# ear-o_board.net
KiCad netlist of a schematic drawn in EAGLE
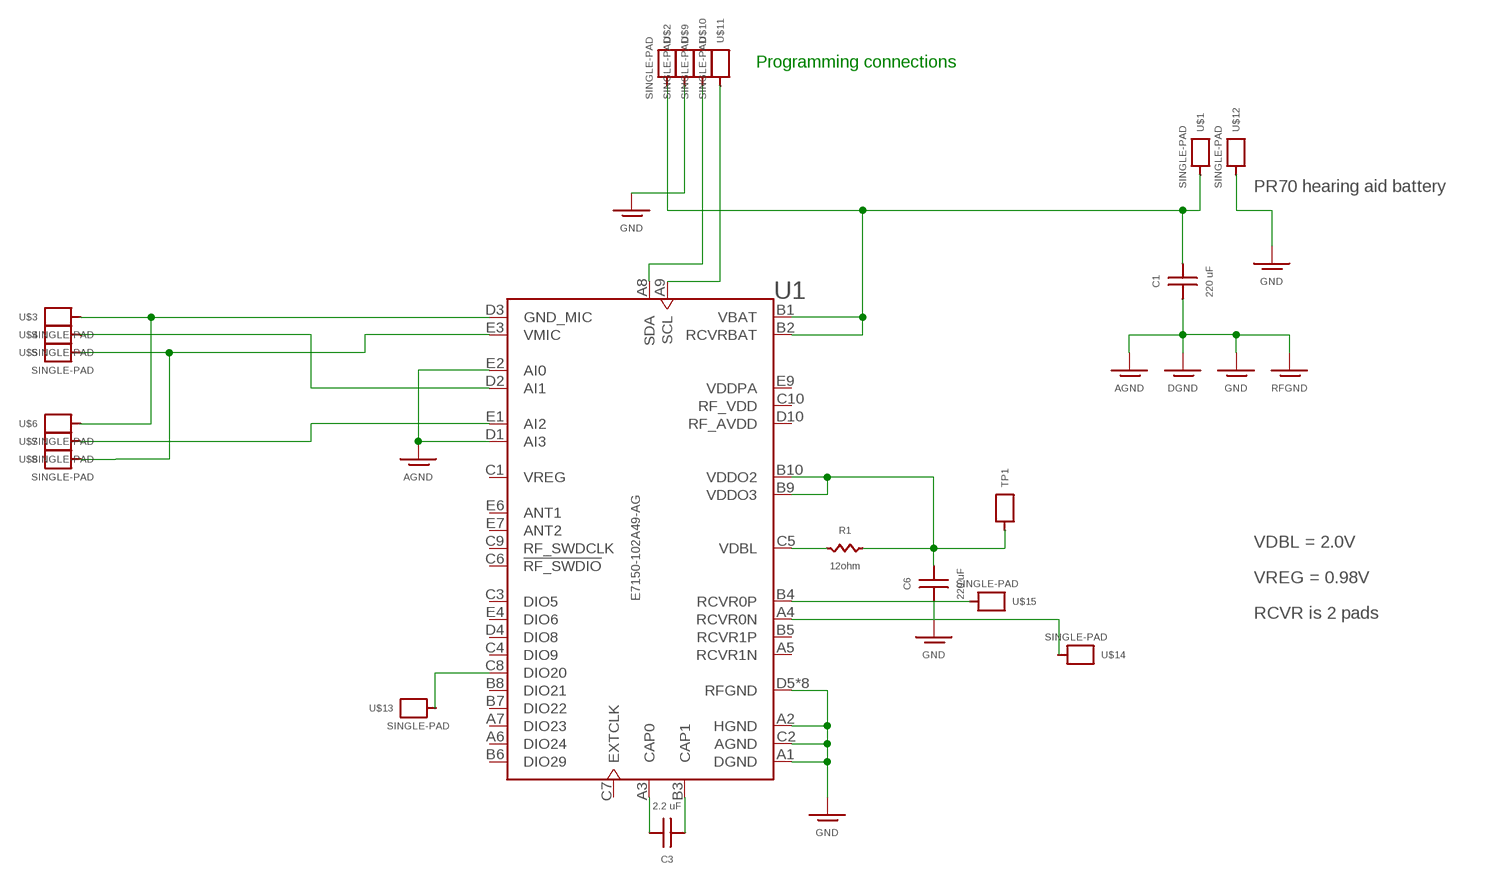
[diagram p0: schematic, sheet 1]

(export (version "E")
  (design (tool "Eeschema 10.0.6"))
  (components
    (comp (ref "C1")
      (value "220 uF")
      (footprint "eagle-import:1206")
      (libsource (lib "eagle-import") (part "C220UF"))
    )
    (comp (ref "C3")
      (value "2.2 uF")
      (footprint "eagle-import:0201")
      (libsource (lib "eagle-import") (part "C2.2UF"))
    )
    (comp (ref "C6")
      (value "220 uF")
      (footprint "eagle-import:1206")
      (libsource (lib "eagle-import") (part "C220UF"))
    )
    (comp (ref "R1")
      (value "12ohm")
      (footprint "eagle-import:0201")
      (libsource (lib "eagle-import") (part "R12OHM"))
    )
    (comp (ref "TP1")
      (value "TEST-POINT")
      (footprint "eagle-import:TEST-PAD-0.2")
      (libsource (lib "eagle-import") (part "TEST-POINT"))
    )
    (comp (ref "U$1")
      (value "SINGLE-PAD")
      (footprint "eagle-import:SINGLE-PAD")
      (libsource (lib "eagle-import") (part "SINGLE-PAD"))
    )
    (comp (ref "U$2")
      (value "SINGLE-PAD")
      (footprint "eagle-import:SINGLE-PAD")
      (libsource (lib "eagle-import") (part "SINGLE-PAD"))
    )
    (comp (ref "U$3")
      (value "SINGLE-PAD")
      (footprint "eagle-import:SINGLE-PAD")
      (libsource (lib "eagle-import") (part "SINGLE-PAD"))
    )
    (comp (ref "U$4")
      (value "SINGLE-PAD")
      (footprint "eagle-import:SINGLE-PAD")
      (libsource (lib "eagle-import") (part "SINGLE-PAD"))
    )
    (comp (ref "U$5")
      (value "SINGLE-PAD")
      (footprint "eagle-import:SINGLE-PAD")
      (libsource (lib "eagle-import") (part "SINGLE-PAD"))
    )
    (comp (ref "U$6")
      (value "SINGLE-PAD")
      (footprint "eagle-import:SINGLE-PAD")
      (libsource (lib "eagle-import") (part "SINGLE-PAD"))
    )
    (comp (ref "U$7")
      (value "SINGLE-PAD")
      (footprint "eagle-import:SINGLE-PAD")
      (libsource (lib "eagle-import") (part "SINGLE-PAD"))
    )
    (comp (ref "U$8")
      (value "SINGLE-PAD")
      (footprint "eagle-import:SINGLE-PAD")
      (libsource (lib "eagle-import") (part "SINGLE-PAD"))
    )
    (comp (ref "U$9")
      (value "SINGLE-PAD")
      (footprint "eagle-import:SINGLE-PAD")
      (libsource (lib "eagle-import") (part "SINGLE-PAD"))
    )
    (comp (ref "U$10")
      (value "SINGLE-PAD")
      (footprint "eagle-import:SINGLE-PAD")
      (libsource (lib "eagle-import") (part "SINGLE-PAD"))
    )
    (comp (ref "U$11")
      (value "SINGLE-PAD")
      (footprint "eagle-import:SINGLE-PAD")
      (libsource (lib "eagle-import") (part "SINGLE-PAD"))
    )
    (comp (ref "U$12")
      (value "SINGLE-PAD")
      (footprint "eagle-import:SINGLE-PAD")
      (libsource (lib "eagle-import") (part "SINGLE-PAD"))
    )
    (comp (ref "U$13")
      (value "SINGLE-PAD")
      (footprint "eagle-import:SINGLE-PAD")
      (libsource (lib "eagle-import") (part "SINGLE-PAD"))
    )
    (comp (ref "U$14")
      (value "SINGLE-PAD")
      (footprint "eagle-import:SINGLE-PAD")
      (libsource (lib "eagle-import") (part "SINGLE-PAD"))
    )
    (comp (ref "U$15")
      (value "SINGLE-PAD")
      (footprint "eagle-import:SINGLE-PAD")
      (libsource (lib "eagle-import") (part "SINGLE-PAD"))
    )
    (comp (ref "U1")
      (value "E7150-102A49-AG")
      (footprint "eagle-import:BGA49C69P10X5_739X394X178")
      (fields (field (name "MANUFACTURER") "ON Semiconductor"))
      (libsource (lib "eagle-import") (part "E7150-102A49-AG"))
    )
  )
  (nets
    (net (code "1") (name "/RF_AVDD") (class "Default")
      (node (ref "U1") (pin "D10") (pinfunction "RF_AVDD_D10") (pintype "power_in"))
    )
    (net (code "2") (name "/RF_VDD") (class "Default")
      (node (ref "U1") (pin "C10") (pinfunction "RF_VDD_C10") (pintype "power_in"))
    )
    (net (code "3") (name "/VDDPA") (class "Default")
      (node (ref "U1") (pin "E9") (pinfunction "VDDPA_E9") (pintype "power_in"))
    )
    (net (code "4") (name "/VREG") (class "Default")
      (node (ref "U1") (pin "C1") (pinfunction "VREG_C1") (pintype "power_in"))
    )
    (net (code "5") (name "AGND") (class "Default")
      (node (ref "C1") (pin "P$1") (pinfunction "1_P$1") (pintype "passive"))
      (node (ref "C6") (pin "P$1") (pinfunction "1_P$1") (pintype "passive"))
      (node (ref "U$12") (pin "P$1") (pinfunction "1_P$1") (pintype "bidirectional"))
      (node (ref "U$9") (pin "P$1") (pinfunction "1_P$1") (pintype "bidirectional"))
      (node (ref "U1") (pin "A1") (pinfunction "DGND_A1") (pintype "power_in"))
      (node (ref "U1") (pin "A2") (pinfunction "HGND_A2") (pintype "power_in"))
      (node (ref "U1") (pin "C2") (pinfunction "AGND_C2") (pintype "power_in"))
      (node (ref "U1") (pin "D1") (pinfunction "AI3_D1") (pintype "input"))
      (node (ref "U1") (pin "D5") (pinfunction "RFGND_D5") (pintype "power_in"))
      (node (ref "U1") (pin "D6") (pinfunction "RFGND_D6") (pintype "power_in"))
      (node (ref "U1") (pin "D7") (pinfunction "RFGND_D7") (pintype "power_in"))
      (node (ref "U1") (pin "D8") (pinfunction "RFGND_D8") (pintype "power_in"))
      (node (ref "U1") (pin "D9") (pinfunction "RFGND_D9") (pintype "power_in"))
      (node (ref "U1") (pin "E10") (pinfunction "RFGND_E10") (pintype "power_in"))
      (node (ref "U1") (pin "E2") (pinfunction "AI0_E2") (pintype "input"))
      (node (ref "U1") (pin "E5") (pinfunction "RFGND_E5") (pintype "power_in"))
      (node (ref "U1") (pin "E8") (pinfunction "RFGND_E8") (pintype "power_in"))
    )
    (net (code "6") (name "Net-(C1-2)") (class "Default")
      (node (ref "C1") (pin "P$2") (pinfunction "2_P$2") (pintype "passive"))
      (node (ref "U$1") (pin "P$1") (pinfunction "1_P$1") (pintype "bidirectional"))
      (node (ref "U$2") (pin "P$1") (pinfunction "1_P$1") (pintype "bidirectional"))
      (node (ref "U1") (pin "B1") (pinfunction "VBAT_B1") (pintype "power_in"))
      (node (ref "U1") (pin "B2") (pinfunction "RCVRBAT_B2") (pintype "power_in"))
    )
    (net (code "7") (name "Net-(C3-1)") (class "Default")
      (node (ref "C3") (pin "P$1") (pinfunction "1_P$1") (pintype "passive"))
      (node (ref "U1") (pin "B3") (pinfunction "CAP1_B3") (pintype "bidirectional"))
    )
    (net (code "8") (name "Net-(C3-2)") (class "Default")
      (node (ref "C3") (pin "P$2") (pinfunction "2_P$2") (pintype "passive"))
      (node (ref "U1") (pin "A3") (pinfunction "CAP0_A3") (pintype "bidirectional"))
    )
    (net (code "9") (name "Net-(C6-2)") (class "Default")
      (node (ref "C6") (pin "P$2") (pinfunction "2_P$2") (pintype "passive"))
      (node (ref "R1") (pin "P$2") (pinfunction "P$2_P$2") (pintype "bidirectional"))
      (node (ref "TP1") (pin "P") (pinfunction "1_P") (pintype "bidirectional"))
      (node (ref "U1") (pin "B10") (pinfunction "VDDO2_B10") (pintype "power_in"))
      (node (ref "U1") (pin "B9") (pinfunction "VDDO3_B9") (pintype "power_in"))
    )
    (net (code "10") (name "Net-(U$3-1)") (class "Default")
      (node (ref "U$3") (pin "P$1") (pinfunction "1_P$1") (pintype "bidirectional"))
      (node (ref "U$6") (pin "P$1") (pinfunction "1_P$1") (pintype "bidirectional"))
      (node (ref "U1") (pin "D3") (pinfunction "GND_MIC_D3") (pintype "power_in"))
    )
    (net (code "11") (name "Net-(U$4-1)") (class "Default")
      (node (ref "U$4") (pin "P$1") (pinfunction "1_P$1") (pintype "bidirectional"))
      (node (ref "U1") (pin "D2") (pinfunction "AI1_D2") (pintype "input"))
    )
    (net (code "12") (name "Net-(U$5-1)") (class "Default")
      (node (ref "U$5") (pin "P$1") (pinfunction "1_P$1") (pintype "bidirectional"))
      (node (ref "U$8") (pin "P$1") (pinfunction "1_P$1") (pintype "bidirectional"))
      (node (ref "U1") (pin "E3") (pinfunction "VMIC_E3") (pintype "power_in"))
    )
    (net (code "13") (name "Net-(U$7-1)") (class "Default")
      (node (ref "U$7") (pin "P$1") (pinfunction "1_P$1") (pintype "bidirectional"))
      (node (ref "U1") (pin "E1") (pinfunction "AI2_E1") (pintype "input"))
    )
    (net (code "14") (name "Net-(U$10-1)") (class "Default")
      (node (ref "U$10") (pin "P$1") (pinfunction "1_P$1") (pintype "bidirectional"))
      (node (ref "U1") (pin "A8") (pinfunction "SDA_A8") (pintype "bidirectional"))
    )
    (net (code "15") (name "Net-(U$11-1)") (class "Default")
      (node (ref "U$11") (pin "P$1") (pinfunction "1_P$1") (pintype "bidirectional"))
      (node (ref "U1") (pin "A9") (pinfunction "SCL_A9") (pintype "input"))
    )
    (net (code "16") (name "Net-(U$13-1)") (class "Default")
      (node (ref "U$13") (pin "P$1") (pinfunction "1_P$1") (pintype "bidirectional"))
      (node (ref "U1") (pin "C8") (pinfunction "DIO20_C8") (pintype "bidirectional"))
    )
    (net (code "17") (name "Net-(U$14-1)") (class "Default")
      (node (ref "U$14") (pin "P$1") (pinfunction "1_P$1") (pintype "bidirectional"))
      (node (ref "U1") (pin "A4") (pinfunction "RCVR0N_A4") (pintype "output"))
    )
    (net (code "18") (name "Net-(U$15-1)") (class "Default")
      (node (ref "U$15") (pin "P$1") (pinfunction "1_P$1") (pintype "bidirectional"))
      (node (ref "U1") (pin "B4") (pinfunction "RCVR0P_B4") (pintype "output"))
    )
    (net (code "19") (name "Net-(U1-VDBL)") (class "Default")
      (node (ref "R1") (pin "P$1") (pinfunction "P$1_P$1") (pintype "bidirectional"))
      (node (ref "U1") (pin "C5") (pinfunction "VDBL_C5") (pintype "output"))
    )
    (net (code "20") (name "unconnected-(U1-ANT1-PadE6)") (class "Default")
      (node (ref "U1") (pin "E6") (pinfunction "ANT1_E6") (pintype "bidirectional"))
    )
    (net (code "21") (name "unconnected-(U1-ANT2-PadE7)") (class "Default")
      (node (ref "U1") (pin "E7") (pinfunction "ANT2_E7") (pintype "bidirectional"))
    )
    (net (code "22") (name "unconnected-(U1-DIO5-PadC3)") (class "Default")
      (node (ref "U1") (pin "C3") (pinfunction "DIO5_C3") (pintype "bidirectional"))
    )
    (net (code "23") (name "unconnected-(U1-DIO6-PadE4)") (class "Default")
      (node (ref "U1") (pin "E4") (pinfunction "DIO6_E4") (pintype "bidirectional"))
    )
    (net (code "24") (name "unconnected-(U1-DIO8-PadD4)") (class "Default")
      (node (ref "U1") (pin "D4") (pinfunction "DIO8_D4") (pintype "bidirectional"))
    )
    (net (code "25") (name "unconnected-(U1-DIO9-PadC4)") (class "Default")
      (node (ref "U1") (pin "C4") (pinfunction "DIO9_C4") (pintype "bidirectional"))
    )
    (net (code "26") (name "unconnected-(U1-DIO21-PadB8)") (class "Default")
      (node (ref "U1") (pin "B8") (pinfunction "DIO21_B8") (pintype "bidirectional"))
    )
    (net (code "27") (name "unconnected-(U1-DIO22-PadB7)") (class "Default")
      (node (ref "U1") (pin "B7") (pinfunction "DIO22_B7") (pintype "bidirectional"))
    )
    (net (code "28") (name "unconnected-(U1-DIO23-PadA7)") (class "Default")
      (node (ref "U1") (pin "A7") (pinfunction "DIO23_A7") (pintype "bidirectional"))
    )
    (net (code "29") (name "unconnected-(U1-DIO24-PadA6)") (class "Default")
      (node (ref "U1") (pin "A6") (pinfunction "DIO24_A6") (pintype "bidirectional"))
    )
    (net (code "30") (name "unconnected-(U1-DIO29-PadB6)") (class "Default")
      (node (ref "U1") (pin "B6") (pinfunction "DIO29_B6") (pintype "bidirectional"))
    )
    (net (code "31") (name "unconnected-(U1-EXTCLK-PadC7)") (class "Default")
      (node (ref "U1") (pin "C7") (pinfunction "EXTCLK_C7") (pintype "input"))
    )
    (net (code "32") (name "unconnected-(U1-RCVR1N-PadA5)") (class "Default")
      (node (ref "U1") (pin "A5") (pinfunction "RCVR1N_A5") (pintype "output"))
    )
    (net (code "33") (name "unconnected-(U1-RCVR1P-PadB5)") (class "Default")
      (node (ref "U1") (pin "B5") (pinfunction "RCVR1P_B5") (pintype "output"))
    )
    (net (code "34") (name "unconnected-(U1-RF_SWDCLK-PadC9)") (class "Default")
      (node (ref "U1") (pin "C9") (pinfunction "RF_SWDCLK_C9") (pintype "bidirectional"))
    )
    (net (code "35") (name "unconnected-(U1-~{RF_SWDIO}-PadC6)") (class "Default")
      (node (ref "U1") (pin "C6") (pinfunction "~{RF_SWDIO}_C6") (pintype "bidirectional"))
    )
  )
)
